# grab.net
KiCad netlist of a schematic drawn in EAGLE
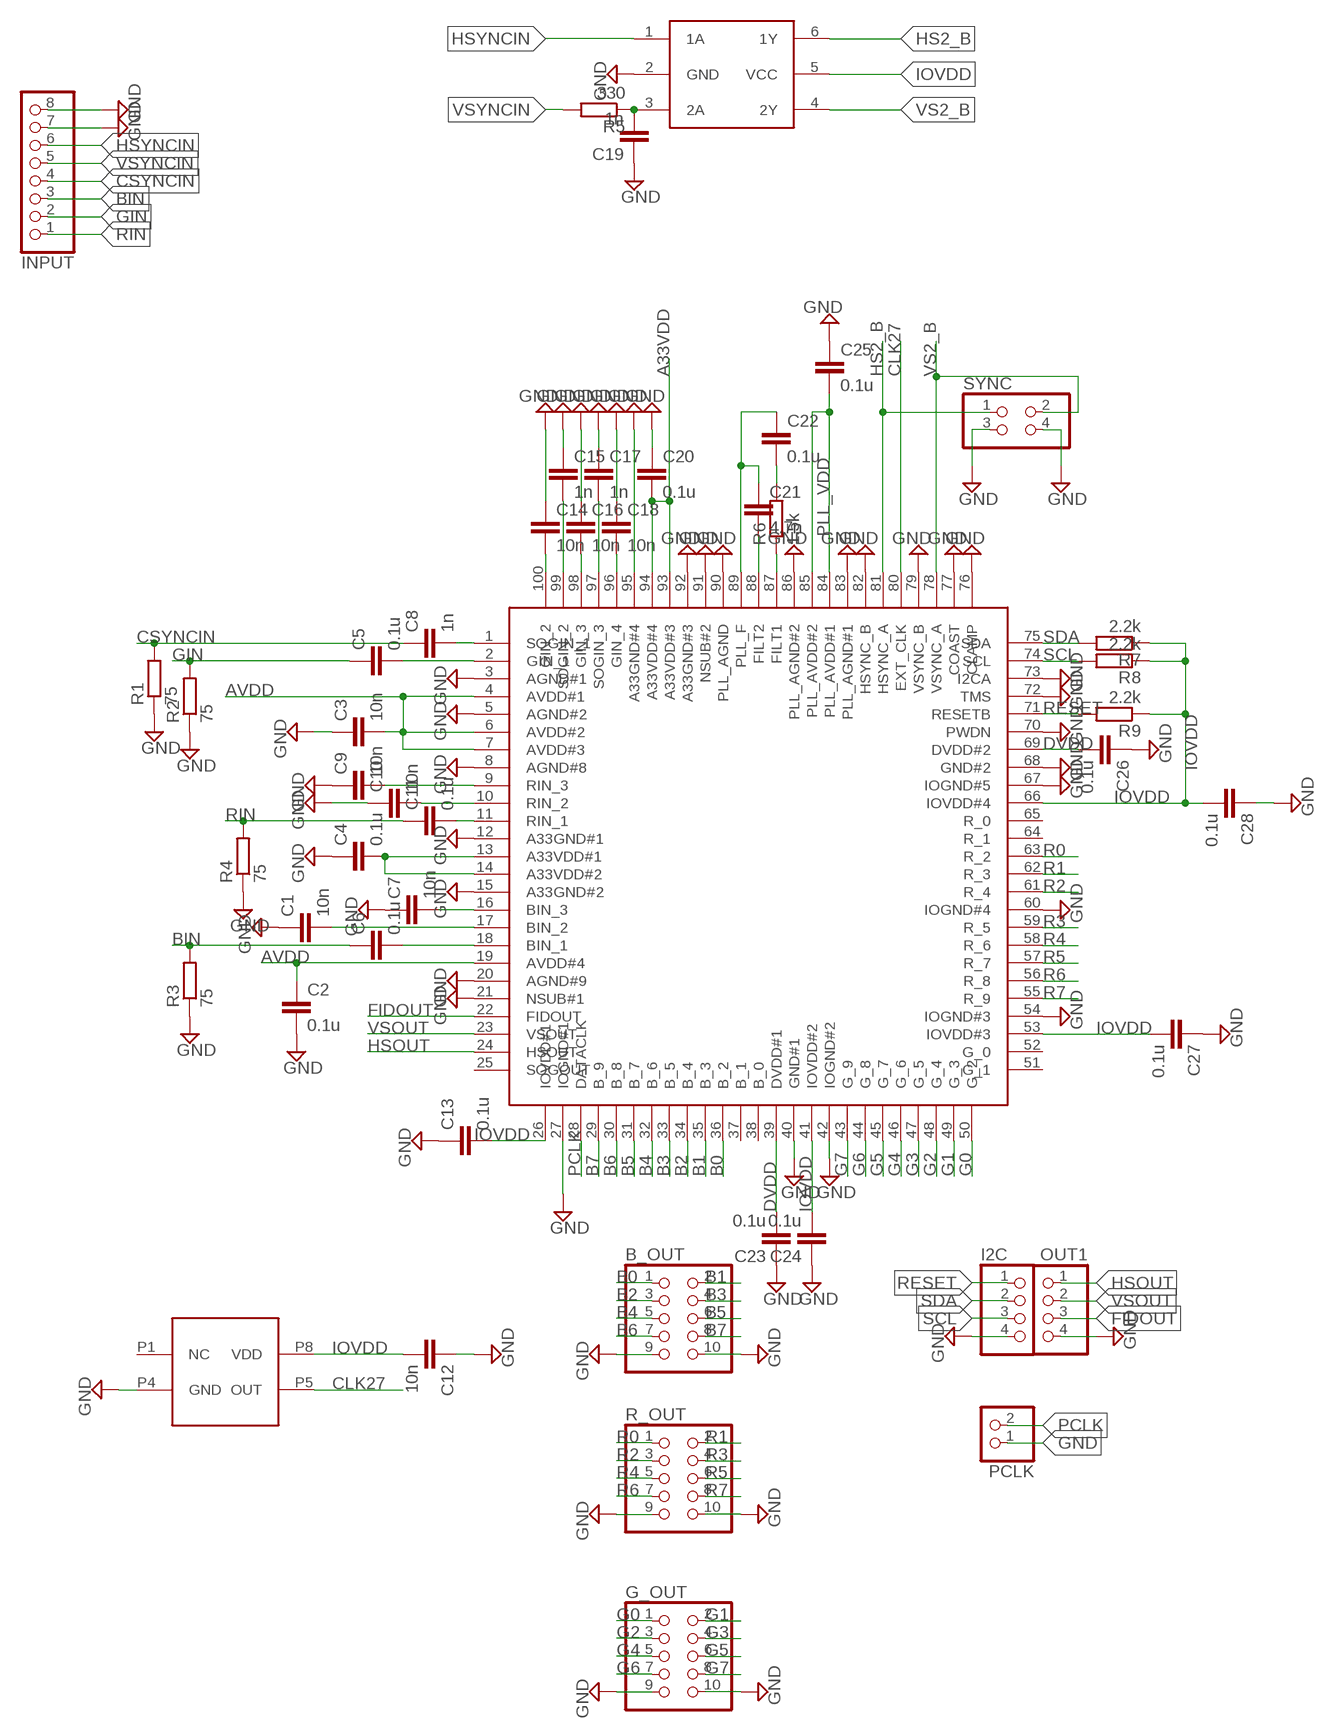
[diagram p0: schematic, sheet 1]
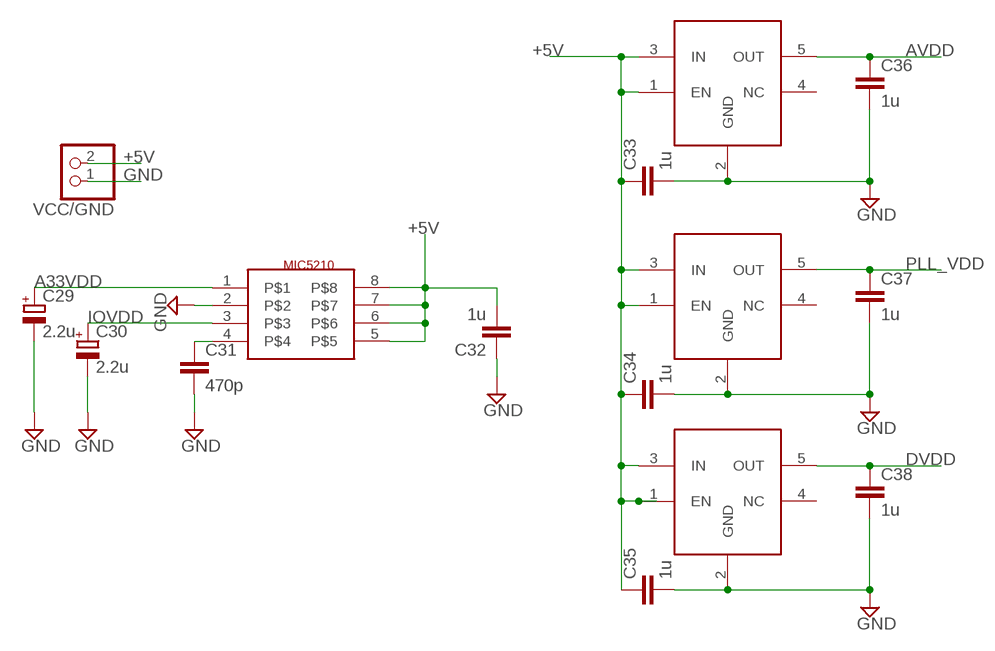
[diagram p1: schematic, sheet 2]

(export (version "E")
  (design (tool "Eeschema 10.0.6"))
  (components
    (comp (ref "27MHZ")
      (value "ACHL-27MHZ-EK")
      (footprint "eagle-import:DIP4")
      (libsource (lib "eagle-import") (part "ACHL-27MHZ-EK"))
    )
    (comp (ref "B_OUT")
      (value "PINHD-2X5")
      (footprint "eagle-import:2X05")
      (libsource (lib "eagle-import") (part "PINHD-2X5"))
    )
    (comp (ref "C1")
      (value "10n")
      (footprint "eagle-import:C0603")
      (libsource (lib "eagle-import") (part "resistor_C-EUC0603"))
    )
    (comp (ref "C2")
      (value "0.1u")
      (footprint "eagle-import:C0603")
      (libsource (lib "eagle-import") (part "resistor_C-EUC0603"))
    )
    (comp (ref "C3")
      (value "10n")
      (footprint "eagle-import:C0603")
      (libsource (lib "eagle-import") (part "resistor_C-EUC0603"))
    )
    (comp (ref "C4")
      (value "0.1u")
      (footprint "eagle-import:C0603")
      (libsource (lib "eagle-import") (part "resistor_C-EUC0603"))
    )
    (comp (ref "C5")
      (value "0.1u")
      (footprint "eagle-import:C0603")
      (libsource (lib "eagle-import") (part "resistor_C-EUC0603"))
    )
    (comp (ref "C6")
      (value "0.1u")
      (footprint "eagle-import:C0603")
      (libsource (lib "eagle-import") (part "resistor_C-EUC0603"))
    )
    (comp (ref "C7")
      (value "10n")
      (footprint "eagle-import:C0603")
      (libsource (lib "eagle-import") (part "resistor_C-EUC0603"))
    )
    (comp (ref "C8")
      (value "1n")
      (footprint "eagle-import:C0603")
      (libsource (lib "eagle-import") (part "resistor_C-EUC0603"))
    )
    (comp (ref "C9")
      (value "10n")
      (footprint "eagle-import:C0603")
      (libsource (lib "eagle-import") (part "resistor_C-EUC0603"))
    )
    (comp (ref "C10")
      (value "10n")
      (footprint "eagle-import:C0603")
      (libsource (lib "eagle-import") (part "resistor_C-EUC0603"))
    )
    (comp (ref "C11")
      (value "0.1u")
      (footprint "eagle-import:C0603")
      (libsource (lib "eagle-import") (part "resistor_C-EUC0603"))
    )
    (comp (ref "C12")
      (value "10n")
      (footprint "eagle-import:C0805")
      (libsource (lib "eagle-import") (part "C-EUC0805"))
    )
    (comp (ref "C13")
      (value "0.1u")
      (footprint "eagle-import:C0603")
      (libsource (lib "eagle-import") (part "resistor_C-EUC0603"))
    )
    (comp (ref "C14")
      (value "10n")
      (footprint "eagle-import:C0603")
      (libsource (lib "eagle-import") (part "resistor_C-EUC0603"))
    )
    (comp (ref "C15")
      (value "1n")
      (footprint "eagle-import:C0603")
      (libsource (lib "eagle-import") (part "resistor_C-EUC0603"))
    )
    (comp (ref "C16")
      (value "10n")
      (footprint "eagle-import:C0603")
      (libsource (lib "eagle-import") (part "resistor_C-EUC0603"))
    )
    (comp (ref "C17")
      (value "1n")
      (footprint "eagle-import:C0603")
      (libsource (lib "eagle-import") (part "resistor_C-EUC0603"))
    )
    (comp (ref "C18")
      (value "10n")
      (footprint "eagle-import:C0603")
      (libsource (lib "eagle-import") (part "resistor_C-EUC0603"))
    )
    (comp (ref "C19")
      (value "1n")
      (footprint "eagle-import:C0805")
      (libsource (lib "eagle-import") (part "C-EUC0805"))
    )
    (comp (ref "C20")
      (value "0.1u")
      (footprint "eagle-import:C0603")
      (libsource (lib "eagle-import") (part "resistor_C-EUC0603"))
    )
    (comp (ref "C21")
      (value "4.7n")
      (footprint "eagle-import:C0603")
      (libsource (lib "eagle-import") (part "resistor_C-EUC0603"))
    )
    (comp (ref "C22")
      (value "0.1u")
      (footprint "eagle-import:C0603")
      (libsource (lib "eagle-import") (part "resistor_C-EUC0603"))
    )
    (comp (ref "C23")
      (value "0.1u")
      (footprint "eagle-import:C0603")
      (libsource (lib "eagle-import") (part "resistor_C-EUC0603"))
    )
    (comp (ref "C24")
      (value "0.1u")
      (footprint "eagle-import:C0603")
      (libsource (lib "eagle-import") (part "resistor_C-EUC0603"))
    )
    (comp (ref "C25")
      (value "0.1u")
      (footprint "eagle-import:C0603")
      (libsource (lib "eagle-import") (part "resistor_C-EUC0603"))
    )
    (comp (ref "C26")
      (value "0.1u")
      (footprint "eagle-import:C0603")
      (libsource (lib "eagle-import") (part "resistor_C-EUC0603"))
    )
    (comp (ref "C27")
      (value "0.1u")
      (footprint "eagle-import:C0603")
      (libsource (lib "eagle-import") (part "resistor_C-EUC0603"))
    )
    (comp (ref "C28")
      (value "0.1u")
      (footprint "eagle-import:C0603")
      (libsource (lib "eagle-import") (part "resistor_C-EUC0603"))
    )
    (comp (ref "G_OUT")
      (value "PINHD-2X5")
      (footprint "eagle-import:2X05")
      (libsource (lib "eagle-import") (part "PINHD-2X5"))
    )
    (comp (ref "I2C")
      (value "PINHD-1X4")
      (footprint "eagle-import:1X04")
      (libsource (lib "eagle-import") (part "PINHD-1X4"))
    )
    (comp (ref "INPUT")
      (value "PINHD-1X8")
      (footprint "eagle-import:1X08")
      (libsource (lib "eagle-import") (part "PINHD-1X8"))
    )
    (comp (ref "OUT1")
      (value "PINHD-1X4")
      (footprint "eagle-import:1X04")
      (libsource (lib "eagle-import") (part "PINHD-1X4"))
    )
    (comp (ref "PCLK")
      (value "PINHD-1X2")
      (footprint "eagle-import:1X02")
      (libsource (lib "eagle-import") (part "PINHD-1X2"))
    )
    (comp (ref "R1")
      (value "75")
      (footprint "eagle-import:R0603")
      (libsource (lib "eagle-import") (part "resistor_R-EU_R0603"))
    )
    (comp (ref "R2")
      (value "75")
      (footprint "eagle-import:R0603")
      (libsource (lib "eagle-import") (part "resistor_R-EU_R0603"))
    )
    (comp (ref "R3")
      (value "75")
      (footprint "eagle-import:R0603")
      (libsource (lib "eagle-import") (part "resistor_R-EU_R0603"))
    )
    (comp (ref "R4")
      (value "75")
      (footprint "eagle-import:R0603")
      (libsource (lib "eagle-import") (part "resistor_R-EU_R0603"))
    )
    (comp (ref "R5")
      (value "330")
      (footprint "eagle-import:R0805")
      (libsource (lib "eagle-import") (part "R-EU_R0805"))
    )
    (comp (ref "R6")
      (value "1.5k")
      (footprint "eagle-import:R0603")
      (libsource (lib "eagle-import") (part "resistor_R-EU_R0603"))
    )
    (comp (ref "R7")
      (value "2.2k")
      (footprint "eagle-import:R0603")
      (libsource (lib "eagle-import") (part "resistor_R-EU_R0603"))
    )
    (comp (ref "R8")
      (value "2.2k")
      (footprint "eagle-import:R0603")
      (libsource (lib "eagle-import") (part "resistor_R-EU_R0603"))
    )
    (comp (ref "R9")
      (value "2.2k")
      (footprint "eagle-import:R0603")
      (libsource (lib "eagle-import") (part "resistor_R-EU_R0603"))
    )
    (comp (ref "R_OUT")
      (value "PINHD-2X5")
      (footprint "eagle-import:2X05")
      (libsource (lib "eagle-import") (part "PINHD-2X5"))
    )
    (comp (ref "SYNC")
      (value "PINHD-2X2")
      (footprint "eagle-import:2X02")
      (libsource (lib "eagle-import") (part "PINHD-2X2"))
    )
    (comp (ref "SYNC_IC")
      (value "SN74LVC2G17SC-70-6")
      (footprint "eagle-import:SC70-6L")
      (libsource (lib "eagle-import") (part "SN74LVC2G17SC-70-6"))
    )
    (comp (ref "TVP7002")
      (value "TVP7002")
      (footprint "eagle-import:TQFP100")
      (libsource (lib "eagle-import") (part "TVP7002"))
    )
    (comp (ref "C29")
      (value "2.2u")
      (footprint "eagle-import:B45181A")
      (libsource (lib "eagle-import") (part "CPOL-EUB45181A"))
    )
    (comp (ref "C30")
      (value "2.2u")
      (footprint "eagle-import:B45181A")
      (libsource (lib "eagle-import") (part "CPOL-EUB45181A"))
    )
    (comp (ref "C31")
      (value "470p")
      (footprint "eagle-import:C0805")
      (libsource (lib "eagle-import") (part "resistor_C-EUC0805"))
    )
    (comp (ref "C32")
      (value "1u")
      (footprint "eagle-import:C0805")
      (libsource (lib "eagle-import") (part "resistor_C-EUC0805"))
    )
    (comp (ref "C33")
      (value "1u")
      (footprint "eagle-import:C0805")
      (libsource (lib "eagle-import") (part "resistor_C-EUC0805"))
    )
    (comp (ref "C34")
      (value "1u")
      (footprint "eagle-import:C0805")
      (libsource (lib "eagle-import") (part "resistor_C-EUC0805"))
    )
    (comp (ref "C35")
      (value "1u")
      (footprint "eagle-import:C0805")
      (libsource (lib "eagle-import") (part "resistor_C-EUC0805"))
    )
    (comp (ref "C36")
      (value "1u")
      (footprint "eagle-import:C0805")
      (libsource (lib "eagle-import") (part "resistor_C-EUC0805"))
    )
    (comp (ref "C37")
      (value "1u")
      (footprint "eagle-import:C0805")
      (libsource (lib "eagle-import") (part "resistor_C-EUC0805"))
    )
    (comp (ref "C38")
      (value "1u")
      (footprint "eagle-import:C0805")
      (libsource (lib "eagle-import") (part "resistor_C-EUC0805"))
    )
    (comp (ref "VCC/GND")
      (value "PINHD-1X2")
      (footprint "eagle-import:1X02")
      (libsource (lib "eagle-import") (part "PINHD-1X2"))
    )
    (comp (ref "VREG1")
      (value "MIC5210MSOP8")
      (footprint "eagle-import:MSOP8")
      (libsource (lib "eagle-import") (part "MIC5210MSOP8"))
    )
    (comp (ref "VREG2")
      (value "TLV70019SOT23-5L")
      (footprint "eagle-import:SOT23-5L")
      (libsource (lib "eagle-import") (part "TLV70019SOT23-5L"))
    )
    (comp (ref "VREG3")
      (value "TLV70019SOT23-5L")
      (footprint "eagle-import:SOT23-5L")
      (libsource (lib "eagle-import") (part "TLV70019SOT23-5L"))
    )
    (comp (ref "VREG4")
      (value "TLV70019SOT23-5L")
      (footprint "eagle-import:SOT23-5L")
      (libsource (lib "eagle-import") (part "TLV70019SOT23-5L"))
    )
  )
  (nets
    (net (code "1") (name "+5V") (class "Default")
      (node (ref "C32") (pin "2") (pinfunction "2_2") (pintype "passive"))
      (node (ref "C33") (pin "1") (pinfunction "1_1") (pintype "passive"))
      (node (ref "C34") (pin "1") (pinfunction "1_1") (pintype "passive"))
      (node (ref "C35") (pin "1") (pinfunction "1_1") (pintype "passive"))
      (node (ref "VCC/GND") (pin "2") (pinfunction "2_2") (pintype "passive"))
      (node (ref "VREG1") (pin "5") (pinfunction "P$5_5") (pintype "bidirectional"))
      (node (ref "VREG1") (pin "6") (pinfunction "P$6_6") (pintype "bidirectional"))
      (node (ref "VREG1") (pin "7") (pinfunction "P$7_7") (pintype "bidirectional"))
      (node (ref "VREG1") (pin "8") (pinfunction "P$8_8") (pintype "bidirectional"))
      (node (ref "VREG2") (pin "1") (pinfunction "EN_1") (pintype "bidirectional"))
      (node (ref "VREG2") (pin "3") (pinfunction "IN_3") (pintype "bidirectional"))
      (node (ref "VREG3") (pin "1") (pinfunction "EN_1") (pintype "bidirectional"))
      (node (ref "VREG3") (pin "3") (pinfunction "IN_3") (pintype "bidirectional"))
      (node (ref "VREG4") (pin "1") (pinfunction "EN_1") (pintype "bidirectional"))
      (node (ref "VREG4") (pin "3") (pinfunction "IN_3") (pintype "bidirectional"))
    )
    (net (code "2") (name "A33VDD") (class "Default")
      (node (ref "C20") (pin "2") (pinfunction "2_2") (pintype "passive"))
      (node (ref "C29") (pin "+") (pinfunction "+_+") (pintype "passive"))
      (node (ref "C4") (pin "2") (pinfunction "2_2") (pintype "passive"))
      (node (ref "TVP7002") (pin "13") (pinfunction "A33VDD#1_13") (pintype "bidirectional"))
      (node (ref "TVP7002") (pin "14") (pinfunction "A33VDD#2_14") (pintype "bidirectional"))
      (node (ref "TVP7002") (pin "93") (pinfunction "A33VDD#3_93") (pintype "bidirectional"))
      (node (ref "TVP7002") (pin "94") (pinfunction "A33VDD#4_94") (pintype "bidirectional"))
      (node (ref "VREG1") (pin "1") (pinfunction "P$1_1") (pintype "bidirectional"))
    )
    (net (code "3") (name "AVDD") (class "Default")
      (node (ref "C2") (pin "1") (pinfunction "1_1") (pintype "passive"))
      (node (ref "C3") (pin "2") (pinfunction "2_2") (pintype "passive"))
      (node (ref "C36") (pin "1") (pinfunction "1_1") (pintype "passive"))
      (node (ref "TVP7002") (pin "19") (pinfunction "AVDD#4_19") (pintype "bidirectional"))
      (node (ref "TVP7002") (pin "4") (pinfunction "AVDD#1_4") (pintype "bidirectional"))
      (node (ref "TVP7002") (pin "6") (pinfunction "AVDD#2_6") (pintype "bidirectional"))
      (node (ref "TVP7002") (pin "7") (pinfunction "AVDD#3_7") (pintype "bidirectional"))
      (node (ref "VREG2") (pin "5") (pinfunction "OUT_5") (pintype "bidirectional"))
    )
    (net (code "4") (name "B0") (class "Default")
      (node (ref "B_OUT") (pin "1") (pinfunction "1_1") (pintype "passive"))
      (node (ref "TVP7002") (pin "36") (pinfunction "B_2_36") (pintype "bidirectional"))
    )
    (net (code "5") (name "B1") (class "Default")
      (node (ref "B_OUT") (pin "2") (pinfunction "2_2") (pintype "passive"))
      (node (ref "TVP7002") (pin "35") (pinfunction "B_3_35") (pintype "bidirectional"))
    )
    (net (code "6") (name "B2") (class "Default")
      (node (ref "B_OUT") (pin "3") (pinfunction "3_3") (pintype "passive"))
      (node (ref "TVP7002") (pin "34") (pinfunction "B_4_34") (pintype "bidirectional"))
    )
    (net (code "7") (name "B3") (class "Default")
      (node (ref "B_OUT") (pin "4") (pinfunction "4_4") (pintype "passive"))
      (node (ref "TVP7002") (pin "33") (pinfunction "B_5_33") (pintype "bidirectional"))
    )
    (net (code "8") (name "B4") (class "Default")
      (node (ref "B_OUT") (pin "5") (pinfunction "5_5") (pintype "passive"))
      (node (ref "TVP7002") (pin "32") (pinfunction "B_6_32") (pintype "bidirectional"))
    )
    (net (code "9") (name "B5") (class "Default")
      (node (ref "B_OUT") (pin "6") (pinfunction "6_6") (pintype "passive"))
      (node (ref "TVP7002") (pin "31") (pinfunction "B_7_31") (pintype "bidirectional"))
    )
    (net (code "10") (name "B6") (class "Default")
      (node (ref "B_OUT") (pin "7") (pinfunction "7_7") (pintype "passive"))
      (node (ref "TVP7002") (pin "30") (pinfunction "B_8_30") (pintype "bidirectional"))
    )
    (net (code "11") (name "B7") (class "Default")
      (node (ref "B_OUT") (pin "8") (pinfunction "8_8") (pintype "passive"))
      (node (ref "TVP7002") (pin "29") (pinfunction "B_9_29") (pintype "bidirectional"))
    )
    (net (code "12") (name "BIN") (class "Default")
      (node (ref "C6") (pin "1") (pinfunction "1_1") (pintype "passive"))
      (node (ref "INPUT") (pin "3") (pinfunction "3_3") (pintype "passive"))
      (node (ref "R3") (pin "2") (pinfunction "2_2") (pintype "passive"))
    )
    (net (code "13") (name "CLK27") (class "Default")
      (node (ref "27MHZ") (pin "P5") (pinfunction "OUT_P5") (pintype "bidirectional"))
      (node (ref "TVP7002") (pin "80") (pinfunction "EXT_CLK_80") (pintype "bidirectional"))
    )
    (net (code "14") (name "CSYNCIN") (class "Default")
      (node (ref "C8") (pin "1") (pinfunction "1_1") (pintype "passive"))
      (node (ref "INPUT") (pin "4") (pinfunction "4_4") (pintype "passive"))
      (node (ref "R1") (pin "2") (pinfunction "2_2") (pintype "passive"))
    )
    (net (code "15") (name "DVDD") (class "Default")
      (node (ref "C23") (pin "2") (pinfunction "2_2") (pintype "passive"))
      (node (ref "C26") (pin "2") (pinfunction "2_2") (pintype "passive"))
      (node (ref "C38") (pin "1") (pinfunction "1_1") (pintype "passive"))
      (node (ref "TVP7002") (pin "39") (pinfunction "DVDD#1_39") (pintype "bidirectional"))
      (node (ref "TVP7002") (pin "69") (pinfunction "DVDD#2_69") (pintype "bidirectional"))
      (node (ref "VREG4") (pin "5") (pinfunction "OUT_5") (pintype "bidirectional"))
    )
    (net (code "16") (name "FIDOUT") (class "Default")
      (node (ref "OUT1") (pin "3") (pinfunction "3_3") (pintype "passive"))
      (node (ref "TVP7002") (pin "22") (pinfunction "FIDOUT_22") (pintype "bidirectional"))
    )
    (net (code "17") (name "G0") (class "Default")
      (node (ref "G_OUT") (pin "1") (pinfunction "1_1") (pintype "passive"))
      (node (ref "TVP7002") (pin "50") (pinfunction "G_2_50") (pintype "bidirectional"))
    )
    (net (code "18") (name "G1") (class "Default")
      (node (ref "G_OUT") (pin "2") (pinfunction "2_2") (pintype "passive"))
      (node (ref "TVP7002") (pin "49") (pinfunction "G_3_49") (pintype "bidirectional"))
    )
    (net (code "19") (name "G2") (class "Default")
      (node (ref "G_OUT") (pin "3") (pinfunction "3_3") (pintype "passive"))
      (node (ref "TVP7002") (pin "48") (pinfunction "G_4_48") (pintype "bidirectional"))
    )
    (net (code "20") (name "G3") (class "Default")
      (node (ref "G_OUT") (pin "4") (pinfunction "4_4") (pintype "passive"))
      (node (ref "TVP7002") (pin "47") (pinfunction "G_5_47") (pintype "bidirectional"))
    )
    (net (code "21") (name "G4") (class "Default")
      (node (ref "G_OUT") (pin "5") (pinfunction "5_5") (pintype "passive"))
      (node (ref "TVP7002") (pin "46") (pinfunction "G_6_46") (pintype "bidirectional"))
    )
    (net (code "22") (name "G5") (class "Default")
      (node (ref "G_OUT") (pin "6") (pinfunction "6_6") (pintype "passive"))
      (node (ref "TVP7002") (pin "45") (pinfunction "G_7_45") (pintype "bidirectional"))
    )
    (net (code "23") (name "G6") (class "Default")
      (node (ref "G_OUT") (pin "7") (pinfunction "7_7") (pintype "passive"))
      (node (ref "TVP7002") (pin "44") (pinfunction "G_8_44") (pintype "bidirectional"))
    )
    (net (code "24") (name "G7") (class "Default")
      (node (ref "G_OUT") (pin "8") (pinfunction "8_8") (pintype "passive"))
      (node (ref "TVP7002") (pin "43") (pinfunction "G_9_43") (pintype "bidirectional"))
    )
    (net (code "25") (name "GIN") (class "Default")
      (node (ref "C5") (pin "1") (pinfunction "1_1") (pintype "passive"))
      (node (ref "INPUT") (pin "2") (pinfunction "2_2") (pintype "passive"))
      (node (ref "R2") (pin "2") (pinfunction "2_2") (pintype "passive"))
    )
    (net (code "26") (name "GND") (class "Default")
      (node (ref "27MHZ") (pin "P4") (pinfunction "GND_P4") (pintype "bidirectional"))
      (node (ref "B_OUT") (pin "10") (pinfunction "10_10") (pintype "passive"))
      (node (ref "B_OUT") (pin "9") (pinfunction "9_9") (pintype "passive"))
      (node (ref "C1") (pin "1") (pinfunction "1_1") (pintype "passive"))
      (node (ref "C10") (pin "1") (pinfunction "1_1") (pintype "passive"))
      (node (ref "C12") (pin "1") (pinfunction "1_1") (pintype "passive"))
      (node (ref "C13") (pin "1") (pinfunction "1_1") (pintype "passive"))
      (node (ref "C14") (pin "1") (pinfunction "1_1") (pintype "passive"))
      (node (ref "C15") (pin "1") (pinfunction "1_1") (pintype "passive"))
      (node (ref "C16") (pin "1") (pinfunction "1_1") (pintype "passive"))
      (node (ref "C17") (pin "1") (pinfunction "1_1") (pintype "passive"))
      (node (ref "C18") (pin "1") (pinfunction "1_1") (pintype "passive"))
      (node (ref "C19") (pin "1") (pinfunction "1_1") (pintype "passive"))
      (node (ref "C2") (pin "2") (pinfunction "2_2") (pintype "passive"))
      (node (ref "C20") (pin "1") (pinfunction "1_1") (pintype "passive"))
      (node (ref "C23") (pin "1") (pinfunction "1_1") (pintype "passive"))
      (node (ref "C24") (pin "1") (pinfunction "1_1") (pintype "passive"))
      (node (ref "C25") (pin "1") (pinfunction "1_1") (pintype "passive"))
      (node (ref "C26") (pin "1") (pinfunction "1_1") (pintype "passive"))
      (node (ref "C27") (pin "1") (pinfunction "1_1") (pintype "passive"))
      (node (ref "C28") (pin "1") (pinfunction "1_1") (pintype "passive"))
      (node (ref "C29") (pin "-") (pinfunction "-_-") (pintype "passive"))
      (node (ref "C3") (pin "1") (pinfunction "1_1") (pintype "passive"))
      (node (ref "C30") (pin "-") (pinfunction "-_-") (pintype "passive"))
      (node (ref "C31") (pin "2") (pinfunction "2_2") (pintype "passive"))
      (node (ref "C32") (pin "1") (pinfunction "1_1") (pintype "passive"))
      (node (ref "C33") (pin "2") (pinfunction "2_2") (pintype "passive"))
      (node (ref "C34") (pin "2") (pinfunction "2_2") (pintype "passive"))
      (node (ref "C35") (pin "2") (pinfunction "2_2") (pintype "passive"))
      (node (ref "C36") (pin "2") (pinfunction "2_2") (pintype "passive"))
      (node (ref "C37") (pin "2") (pinfunction "2_2") (pintype "passive"))
      (node (ref "C38") (pin "2") (pinfunction "2_2") (pintype "passive"))
      (node (ref "C4") (pin "1") (pinfunction "1_1") (pintype "passive"))
      (node (ref "C7") (pin "1") (pinfunction "1_1") (pintype "passive"))
      (node (ref "C9") (pin "1") (pinfunction "1_1") (pintype "passive"))
      (node (ref "G_OUT") (pin "10") (pinfunction "10_10") (pintype "passive"))
      (node (ref "G_OUT") (pin "9") (pinfunction "9_9") (pintype "passive"))
      (node (ref "I2C") (pin "4") (pinfunction "4_4") (pintype "passive"))
      (node (ref "INPUT") (pin "7") (pinfunction "7_7") (pintype "passive"))
      (node (ref "INPUT") (pin "8") (pinfunction "8_8") (pintype "passive"))
      (node (ref "OUT1") (pin "4") (pinfunction "4_4") (pintype "passive"))
      (node (ref "PCLK") (pin "1") (pinfunction "1_1") (pintype "passive"))
      (node (ref "R1") (pin "1") (pinfunction "1_1") (pintype "passive"))
      (node (ref "R2") (pin "1") (pinfunction "1_1") (pintype "passive"))
      (node (ref "R3") (pin "1") (pinfunction "1_1") (pintype "passive"))
      (node (ref "R4") (pin "1") (pinfunction "1_1") (pintype "passive"))
      (node (ref "R_OUT") (pin "10") (pinfunction "10_10") (pintype "passive"))
      (node (ref "R_OUT") (pin "9") (pinfunction "9_9") (pintype "passive"))
      (node (ref "SYNC") (pin "3") (pinfunction "3_3") (pintype "passive"))
      (node (ref "SYNC") (pin "4") (pinfunction "4_4") (pintype "passive"))
      (node (ref "SYNC_IC") (pin "2") (pinfunction "GND_2") (pintype "bidirectional"))
      (node (ref "TVP7002") (pin "12") (pinfunction "A33GND#1_12") (pintype "bidirectional"))
      (node (ref "TVP7002") (pin "15") (pinfunction "A33GND#2_15") (pintype "bidirectional"))
      (node (ref "TVP7002") (pin "20") (pinfunction "AGND#9_20") (pintype "bidirectional"))
      (node (ref "TVP7002") (pin "21") (pinfunction "NSUB#1_21") (pintype "bidirectional"))
      (node (ref "TVP7002") (pin "27") (pinfunction "IOGND#1_27") (pintype "bidirectional"))
      (node (ref "TVP7002") (pin "3") (pinfunction "AGND#1_3") (pintype "bidirectional"))
      (node (ref "TVP7002") (pin "40") (pinfunction "GND#1_40") (pintype "bidirectional"))
      (node (ref "TVP7002") (pin "42") (pinfunction "IOGND#2_42") (pintype "bidirectional"))
      (node (ref "TVP7002") (pin "5") (pinfunction "AGND#2_5") (pintype "bidirectional"))
      (node (ref "TVP7002") (pin "54") (pinfunction "IOGND#3_54") (pintype "bidirectional"))
      (node (ref "TVP7002") (pin "60") (pinfunction "IOGND#4_60") (pintype "bidirectional"))
      (node (ref "TVP7002") (pin "67") (pinfunction "IOGND#5_67") (pintype "bidirectional"))
      (node (ref "TVP7002") (pin "68") (pinfunction "GND#2_68") (pintype "bidirectional"))
      (node (ref "TVP7002") (pin "70") (pinfunction "PWDN_70") (pintype "bidirectional"))
      (node (ref "TVP7002") (pin "72") (pinfunction "TMS_72") (pintype "bidirectional"))
      (node (ref "TVP7002") (pin "73") (pinfunction "I2CA_73") (pintype "bidirectional"))
      (node (ref "TVP7002") (pin "76") (pinfunction "CLAMP_76") (pintype "bidirectional"))
      (node (ref "TVP7002") (pin "77") (pinfunction "COAST_77") (pintype "bidirectional"))
      (node (ref "TVP7002") (pin "79") (pinfunction "VSYNC_B_79") (pintype "bidirectional"))
      (node (ref "TVP7002") (pin "8") (pinfunction "AGND#8_8") (pintype "bidirectional"))
      (node (ref "TVP7002") (pin "82") (pinfunction "HSYNC_B_82") (pintype "bidirectional"))
      (node (ref "TVP7002") (pin "83") (pinfunction "PLL_AGND#1_83") (pintype "bidirectional"))
      (node (ref "TVP7002") (pin "86") (pinfunction "PLL_AGND#2_86") (pintype "bidirectional"))
      (node (ref "TVP7002") (pin "90") (pinfunction "PLL_AGND_90") (pintype "bidirectional"))
      (node (ref "TVP7002") (pin "91") (pinfunction "NSUB#2_91") (pintype "bidirectional"))
      (node (ref "TVP7002") (pin "92") (pinfunction "A33GND#3_92") (pintype "bidirectional"))
      (node (ref "TVP7002") (pin "95") (pinfunction "A33GND#4_95") (pintype "bidirectional"))
      (node (ref "VCC/GND") (pin "1") (pinfunction "1_1") (pintype "passive"))
      (node (ref "VREG1") (pin "2") (pinfunction "P$2_2") (pintype "bidirectional"))
      (node (ref "VREG2") (pin "2") (pinfunction "GND_2") (pintype "bidirectional"))
      (node (ref "VREG3") (pin "2") (pinfunction "GND_2") (pintype "bidirectional"))
      (node (ref "VREG4") (pin "2") (pinfunction "GND_2") (pintype "bidirectional"))
    )
    (net (code "27") (name "HS2_B") (class "Default")
      (node (ref "SYNC") (pin "1") (pinfunction "1_1") (pintype "passive"))
      (node (ref "SYNC_IC") (pin "6") (pinfunction "1Y_6") (pintype "bidirectional"))
      (node (ref "TVP7002") (pin "81") (pinfunction "HSYNC_A_81") (pintype "bidirectional"))
    )
    (net (code "28") (name "HSOUT") (class "Default")
      (node (ref "OUT1") (pin "1") (pinfunction "1_1") (pintype "passive"))
      (node (ref "TVP7002") (pin "24") (pinfunction "HSOUT_24") (pintype "bidirectional"))
    )
    (net (code "29") (name "HSYNCIN") (class "Default")
      (node (ref "INPUT") (pin "6") (pinfunction "6_6") (pintype "passive"))
      (node (ref "SYNC_IC") (pin "1") (pinfunction "1A_1") (pintype "bidirectional"))
    )
    (net (code "30") (name "IOVDD") (class "Default")
      (node (ref "27MHZ") (pin "P8") (pinfunction "VDD_P8") (pintype "bidirectional"))
      (node (ref "C12") (pin "2") (pinfunction "2_2") (pintype "passive"))
      (node (ref "C13") (pin "2") (pinfunction "2_2") (pintype "passive"))
      (node (ref "C24") (pin "2") (pinfunction "2_2") (pintype "passive"))
      (node (ref "C27") (pin "2") (pinfunction "2_2") (pintype "passive"))
      (node (ref "C28") (pin "2") (pinfunction "2_2") (pintype "passive"))
      (node (ref "C30") (pin "+") (pinfunction "+_+") (pintype "passive"))
      (node (ref "R7") (pin "1") (pinfunction "1_1") (pintype "passive"))
      (node (ref "R8") (pin "1") (pinfunction "1_1") (pintype "passive"))
      (node (ref "R9") (pin "1") (pinfunction "1_1") (pintype "passive"))
      (node (ref "SYNC_IC") (pin "5") (pinfunction "VCC_5") (pintype "bidirectional"))
      (node (ref "TVP7002") (pin "26") (pinfunction "IOVDD#1_26") (pintype "bidirectional"))
      (node (ref "TVP7002") (pin "41") (pinfunction "IOVDD#2_41") (pintype "bidirectional"))
      (node (ref "TVP7002") (pin "53") (pinfunction "IOVDD#3_53") (pintype "bidirectional"))
      (node (ref "TVP7002") (pin "66") (pinfunction "IOVDD#4_66") (pintype "bidirectional"))
      (node (ref "VREG1") (pin "3") (pinfunction "P$3_3") (pintype "bidirectional"))
    )
    (net (code "31") (name "Net-(C22-Pad2)") (class "Default")
      (node (ref "C22") (pin "2") (pinfunction "2_2") (pintype "passive"))
      (node (ref "R6") (pin "2") (pinfunction "2_2") (pintype "passive"))
    )
    (net (code "32") (name "Net-(SYNC_IC-2A)") (class "Default")
      (node (ref "C19") (pin "2") (pinfunction "2_2") (pintype "passive"))
      (node (ref "R5") (pin "1") (pinfunction "1_1") (pintype "passive"))
      (node (ref "SYNC_IC") (pin "3") (pinfunction "2A_3") (pintype "bidirectional"))
    )
    (net (code "33") (name "Net-(TVP7002-BIN_1)") (class "Default")
      (node (ref "C6") (pin "2") (pinfunction "2_2") (pintype "passive"))
      (node (ref "TVP7002") (pin "18") (pinfunction "BIN_1_18") (pintype "bidirectional"))
    )
    (net (code "34") (name "Net-(TVP7002-BIN_2)") (class "Default")
      (node (ref "C1") (pin "2") (pinfunction "2_2") (pintype "passive"))
      (node (ref "TVP7002") (pin "17") (pinfunction "BIN_2_17") (pintype "bidirectional"))
    )
    (net (code "35") (name "Net-(TVP7002-BIN_3)") (class "Default")
      (node (ref "C7") (pin "2") (pinfunction "2_2") (pintype "passive"))
      (node (ref "TVP7002") (pin "16") (pinfunction "BIN_3_16") (pintype "bidirectional"))
    )
    (net (code "36") (name "Net-(TVP7002-FILT1)") (class "Default")
      (node (ref "R6") (pin "1") (pinfunction "1_1") (pintype "passive"))
      (node (ref "TVP7002") (pin "87") (pinfunction "FILT1_87") (pintype "bidirectional"))
    )
    (net (code "37") (name "Net-(TVP7002-FILT2)") (class "Default")
      (node (ref "C21") (pin "2") (pinfunction "2_2") (pintype "passive"))
      (node (ref "TVP7002") (pin "88") (pinfunction "FILT2_88") (pintype "bidirectional"))
    )
    (net (code "38") (name "Net-(TVP7002-GIN_1)") (class "Default")
      (node (ref "C5") (pin "2") (pinfunction "2_2") (pintype "passive"))
      (node (ref "TVP7002") (pin "2") (pinfunction "GIN_1_2") (pintype "bidirectional"))
    )
    (net (code "39") (name "Net-(TVP7002-GIN_2)") (class "Default")
      (node (ref "C14") (pin "2") (pinfunction "2_2") (pintype "passive"))
      (node (ref "TVP7002") (pin "100") (pinfunction "GIN_2_100") (pintype "bidirectional"))
    )
    (net (code "40") (name "Net-(TVP7002-GIN_3)") (class "Default")
      (node (ref "C16") (pin "2") (pinfunction "2_2") (pintype "passive"))
      (node (ref "TVP7002") (pin "98") (pinfunction "GIN_3_98") (pintype "bidirectional"))
    )
    (net (code "41") (name "Net-(TVP7002-GIN_4)") (class "Default")
      (node (ref "C18") (pin "2") (pinfunction "2_2") (pintype "passive"))
      (node (ref "TVP7002") (pin "96") (pinfunction "GIN_4_96") (pintype "bidirectional"))
    )
    (net (code "42") (name "Net-(TVP7002-PLL_F)") (class "Default")
      (node (ref "C21") (pin "1") (pinfunction "1_1") (pintype "passive"))
      (node (ref "C22") (pin "1") (pinfunction "1_1") (pintype "passive"))
      (node (ref "TVP7002") (pin "89") (pinfunction "PLL_F_89") (pintype "bidirectional"))
    )
    (net (code "43") (name "Net-(TVP7002-RIN_1)") (class "Default")
      (node (ref "C11") (pin "2") (pinfunction "2_2") (pintype "passive"))
      (node (ref "TVP7002") (pin "11") (pinfunction "RIN_1_11") (pintype "bidirectional"))
    )
    (net (code "44") (name "Net-(TVP7002-RIN_2)") (class "Default")
      (node (ref "C10") (pin "2") (pinfunction "2_2") (pintype "passive"))
      (node (ref "TVP7002") (pin "10") (pinfunction "RIN_2_10") (pintype "bidirectional"))
    )
    (net (code "45") (name "Net-(TVP7002-RIN_3)") (class "Default")
      (node (ref "C9") (pin "2") (pinfunction "2_2") (pintype "passive"))
      (node (ref "TVP7002") (pin "9") (pinfunction "RIN_3_9") (pintype "bidirectional"))
    )
    (net (code "46") (name "Net-(TVP7002-SOGIN_1)") (class "Default")
      (node (ref "C8") (pin "2") (pinfunction "2_2") (pintype "passive"))
      (node (ref "TVP7002") (pin "1") (pinfunction "SOGIN_1_1") (pintype "bidirectional"))
    )
    (net (code "47") (name "Net-(TVP7002-SOGIN_2)") (class "Default")
      (node (ref "C15") (pin "2") (pinfunction "2_2") (pintype "passive"))
      (node (ref "TVP7002") (pin "99") (pinfunction "SOGIN_2_99") (pintype "bidirectional"))
    )
    (net (code "48") (name "Net-(TVP7002-SOGIN_3)") (class "Default")
      (node (ref "C17") (pin "2") (pinfunction "2_2") (pintype "passive"))
      (node (ref "TVP7002") (pin "97") (pinfunction "SOGIN_3_97") (pintype "bidirectional"))
    )
    (net (code "49") (name "Net-(VREG1-P$4)") (class "Default")
      (node (ref "C31") (pin "1") (pinfunction "1_1") (pintype "passive"))
      (node (ref "VREG1") (pin "4") (pinfunction "P$4_4") (pintype "bidirectional"))
    )
    (net (code "50") (name "PCLK") (class "Default")
      (node (ref "PCLK") (pin "2") (pinfunction "2_2") (pintype "passive"))
      (node (ref "TVP7002") (pin "28") (pinfunction "DATACLK_28") (pintype "bidirectional"))
    )
    (net (code "51") (name "PLL_VDD") (class "Default")
      (node (ref "C25") (pin "2") (pinfunction "2_2") (pintype "passive"))
      (node (ref "C37") (pin "1") (pinfunction "1_1") (pintype "passive"))
      (node (ref "TVP7002") (pin "84") (pinfunction "PLL_AVDD#1_84") (pintype "bidirectional"))
      (node (ref "TVP7002") (pin "85") (pinfunction "PLL_AVDD#2_85") (pintype "bidirectional"))
      (node (ref "VREG3") (pin "5") (pinfunction "OUT_5") (pintype "bidirectional"))
    )
    (net (code "52") (name "R0") (class "Default")
      (node (ref "R_OUT") (pin "1") (pinfunction "1_1") (pintype "passive"))
      (node (ref "TVP7002") (pin "63") (pinfunction "R_2_63") (pintype "bidirectional"))
    )
    (net (code "53") (name "R1") (class "Default")
      (node (ref "R_OUT") (pin "2") (pinfunction "2_2") (pintype "passive"))
      (node (ref "TVP7002") (pin "62") (pinfunction "R_3_62") (pintype "bidirectional"))
    )
    (net (code "54") (name "R2") (class "Default")
      (node (ref "R_OUT") (pin "3") (pinfunction "3_3") (pintype "passive"))
      (node (ref "TVP7002") (pin "61") (pinfunction "R_4_61") (pintype "bidirectional"))
    )
    (net (code "55") (name "R3") (class "Default")
      (node (ref "R_OUT") (pin "4") (pinfunction "4_4") (pintype "passive"))
      (node (ref "TVP7002") (pin "59") (pinfunction "R_5_59") (pintype "bidirectional"))
    )
    (net (code "56") (name "R4") (class "Default")
      (node (ref "R_OUT") (pin "5") (pinfunction "5_5") (pintype "passive"))
      (node (ref "TVP7002") (pin "58") (pinfunction "R_6_58") (pintype "bidirectional"))
    )
    (net (code "57") (name "R5") (class "Default")
      (node (ref "R_OUT") (pin "6") (pinfunction "6_6") (pintype "passive"))
      (node (ref "TVP7002") (pin "57") (pinfunction "R_7_57") (pintype "bidirectional"))
    )
    (net (code "58") (name "R6") (class "Default")
      (node (ref "R_OUT") (pin "7") (pinfunction "7_7") (pintype "passive"))
      (node (ref "TVP7002") (pin "56") (pinfunction "R_8_56") (pintype "bidirectional"))
    )
    (net (code "59") (name "R7") (class "Default")
      (node (ref "R_OUT") (pin "8") (pinfunction "8_8") (pintype "passive"))
      (node (ref "TVP7002") (pin "55") (pinfunction "R_9_55") (pintype "bidirectional"))
    )
    (net (code "60") (name "RESET") (class "Default")
      (node (ref "I2C") (pin "1") (pinfunction "1_1") (pintype "passive"))
      (node (ref "R9") (pin "2") (pinfunction "2_2") (pintype "passive"))
      (node (ref "TVP7002") (pin "71") (pinfunction "RESETB_71") (pintype "bidirectional"))
    )
    (net (code "61") (name "RIN") (class "Default")
      (node (ref "C11") (pin "1") (pinfunction "1_1") (pintype "passive"))
      (node (ref "INPUT") (pin "1") (pinfunction "1_1") (pintype "passive"))
      (node (ref "R4") (pin "2") (pinfunction "2_2") (pintype "passive"))
    )
    (net (code "62") (name "SCL") (class "Default")
      (node (ref "I2C") (pin "3") (pinfunction "3_3") (pintype "passive"))
      (node (ref "R8") (pin "2") (pinfunction "2_2") (pintype "passive"))
      (node (ref "TVP7002") (pin "74") (pinfunction "SCL_74") (pintype "bidirectional"))
    )
    (net (code "63") (name "SDA") (class "Default")
      (node (ref "I2C") (pin "2") (pinfunction "2_2") (pintype "passive"))
      (node (ref "R7") (pin "2") (pinfunction "2_2") (pintype "passive"))
      (node (ref "TVP7002") (pin "75") (pinfunction "SDA_75") (pintype "bidirectional"))
    )
    (net (code "64") (name "VS2_B") (class "Default")
      (node (ref "SYNC") (pin "2") (pinfunction "2_2") (pintype "passive"))
      (node (ref "SYNC_IC") (pin "4") (pinfunction "2Y_4") (pintype "bidirectional"))
      (node (ref "TVP7002") (pin "78") (pinfunction "VSYNC_A_78") (pintype "bidirectional"))
    )
    (net (code "65") (name "VSOUT") (class "Default")
      (node (ref "OUT1") (pin "2") (pinfunction "2_2") (pintype "passive"))
      (node (ref "TVP7002") (pin "23") (pinfunction "VSOUT_23") (pintype "bidirectional"))
    )
    (net (code "66") (name "VSYNCIN") (class "Default")
      (node (ref "INPUT") (pin "5") (pinfunction "5_5") (pintype "passive"))
      (node (ref "R5") (pin "2") (pinfunction "2_2") (pintype "passive"))
    )
    (net (code "67") (name "unconnected-(27MHZ-NC-PadP1)") (class "Default")
      (node (ref "27MHZ") (pin "P1") (pinfunction "NC_P1") (pintype "bidirectional"))
    )
    (net (code "68") (name "unconnected-(TVP7002-B_0-Pad38)") (class "Default")
      (node (ref "TVP7002") (pin "38") (pinfunction "B_0_38") (pintype "bidirectional"))
    )
    (net (code "69") (name "unconnected-(TVP7002-B_1-Pad37)") (class "Default")
      (node (ref "TVP7002") (pin "37") (pinfunction "B_1_37") (pintype "bidirectional"))
    )
    (net (code "70") (name "unconnected-(TVP7002-G_0-Pad52)") (class "Default")
      (node (ref "TVP7002") (pin "52") (pinfunction "G_0_52") (pintype "bidirectional"))
    )
    (net (code "71") (name "unconnected-(TVP7002-G_1-Pad51)") (class "Default")
      (node (ref "TVP7002") (pin "51") (pinfunction "G_1_51") (pintype "bidirectional"))
    )
    (net (code "72") (name "unconnected-(TVP7002-R_0-Pad65)") (class "Default")
      (node (ref "TVP7002") (pin "65") (pinfunction "R_0_65") (pintype "bidirectional"))
    )
    (net (code "73") (name "unconnected-(TVP7002-R_1-Pad64)") (class "Default")
      (node (ref "TVP7002") (pin "64") (pinfunction "R_1_64") (pintype "bidirectional"))
    )
    (net (code "74") (name "unconnected-(TVP7002-SOGOUT-Pad25)") (class "Default")
      (node (ref "TVP7002") (pin "25") (pinfunction "SOGOUT_25") (pintype "bidirectional"))
    )
    (net (code "75") (name "unconnected-(VREG2-NC-Pad4)") (class "Default")
      (node (ref "VREG2") (pin "4") (pinfunction "NC_4") (pintype "bidirectional"))
    )
    (net (code "76") (name "unconnected-(VREG3-NC-Pad4)") (class "Default")
      (node (ref "VREG3") (pin "4") (pinfunction "NC_4") (pintype "bidirectional"))
    )
    (net (code "77") (name "unconnected-(VREG4-NC-Pad4)") (class "Default")
      (node (ref "VREG4") (pin "4") (pinfunction "NC_4") (pintype "bidirectional"))
    )
  )
)
